# ATJ3315Recorder.net
KiCad netlist of a schematic drawn in EAGLE
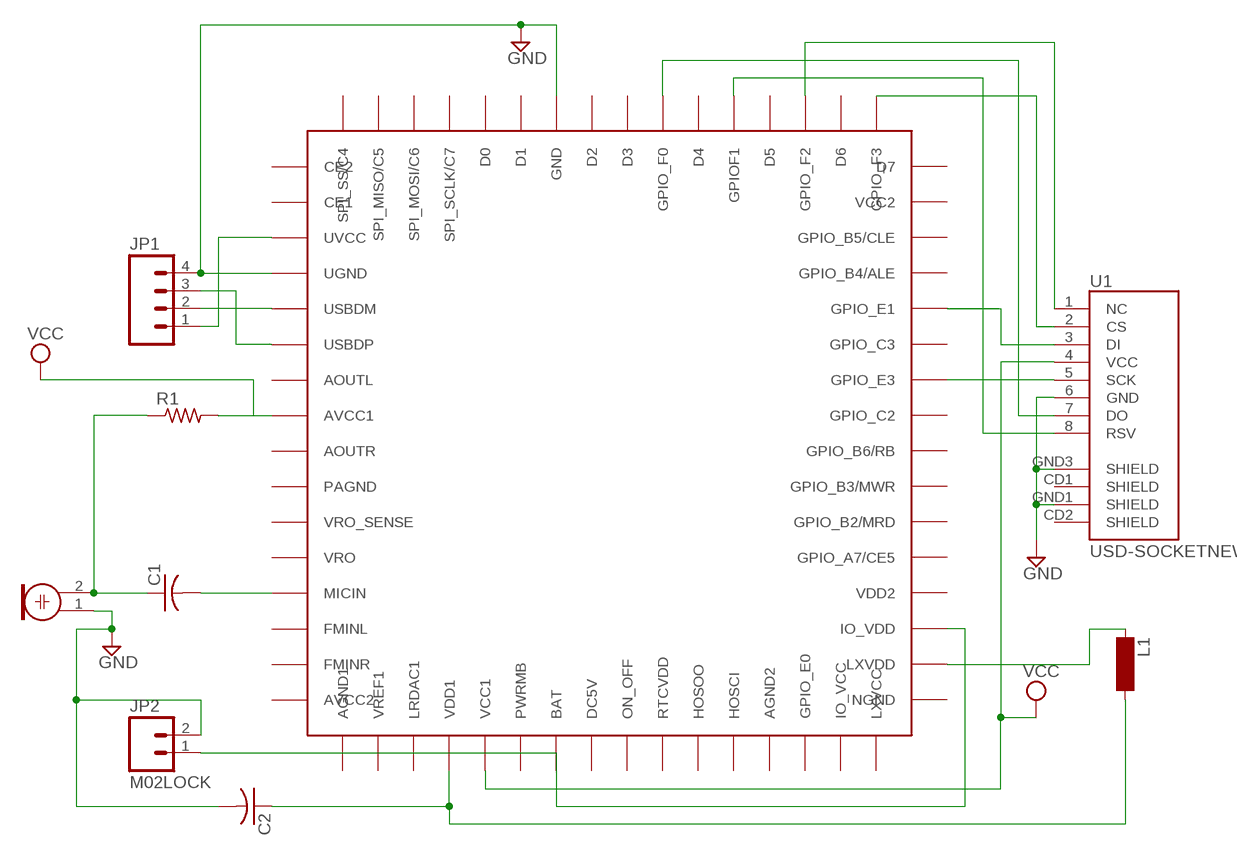
[diagram p0: schematic, sheet 1]

(export (version "E")
  (design (tool "Eeschema 10.0.6"))
  (components
    (comp (ref "C1")
      (value "C-USC0201")
      (footprint "eagle-import:C0201")
      (libsource (lib "eagle-import") (part "C-USC0201"))
    )
    (comp (ref "C2")
      (value "C-USC0201")
      (footprint "eagle-import:C0201")
      (libsource (lib "eagle-import") (part "C-USC0201"))
    )
    (comp (ref "JP1")
      (value "M04PTH")
      (footprint "eagle-import:1X04")
      (libsource (lib "eagle-import") (part "M04PTH"))
    )
    (comp (ref "JP2")
      (value "M02LOCK")
      (footprint "eagle-import:1X02_LOCK")
      (libsource (lib "eagle-import") (part "M02LOCK"))
    )
    (comp (ref "L1")
      (value "SM-1206")
      (footprint "eagle-import:SM-1206")
      (libsource (lib "eagle-import") (part "SM-1206"))
    )
    (comp (ref "M1")
      (value "ELECTRET_MICROPHON-WM-61A")
      (footprint "eagle-import:WM-61A")
      (libsource (lib "eagle-import") (part "ELECTRET_MICROPHON-WM-61A"))
    )
    (comp (ref "R1")
      (value "R-US_M0805")
      (footprint "eagle-import:M0805")
      (libsource (lib "eagle-import") (part "R-US_M0805"))
    )
    (comp (ref "U$4")
      (value "AJ3315")
      (footprint "eagle-import:64M1")
      (libsource (lib "eagle-import") (part "AJ3315"))
    )
    (comp (ref "U1")
      (value "USD-SOCKETNEW")
      (footprint "eagle-import:MICRO-SD-SOCKET-PP")
      (libsource (lib "eagle-import") (part "USD-SOCKETNEW"))
    )
  )
  (nets
    (net (code "1") (name "GND") (class "Default")
      (node (ref "C2") (pin "2") (pinfunction "2_2") (pintype "passive"))
      (node (ref "JP1") (pin "4") (pinfunction "4_4") (pintype "passive"))
      (node (ref "JP2") (pin "2") (pinfunction "2_2") (pintype "passive"))
      (node (ref "M1") (pin "1") (pinfunction "1_1") (pintype "passive"))
      (node (ref "U$4") (pin "4") (pinfunction "UGND_4") (pintype "bidirectional"))
      (node (ref "U$4") (pin "58") (pinfunction "GND_58") (pintype "bidirectional"))
      (node (ref "U1") (pin "6") (pinfunction "GND_6") (pintype "bidirectional"))
      (node (ref "U1") (pin "GND1") (pinfunction "SHIELD_GND1") (pintype "bidirectional"))
      (node (ref "U1") (pin "GND3") (pinfunction "SHIELD_GND3") (pintype "bidirectional"))
    )
    (net (code "2") (name "Net-(C1-Pad1)") (class "Default")
      (node (ref "C1") (pin "1") (pinfunction "1_1") (pintype "passive"))
      (node (ref "M1") (pin "2") (pinfunction "2_2") (pintype "passive"))
      (node (ref "R1") (pin "1") (pinfunction "1_1") (pintype "passive"))
    )
    (net (code "3") (name "Net-(U$4-AVCC1)") (class "Default")
      (node (ref "R1") (pin "2") (pinfunction "2_2") (pintype "passive"))
      (node (ref "U$4") (pin "8") (pinfunction "AVCC1_8") (pintype "bidirectional"))
    )
    (net (code "4") (name "Net-(U$4-BAT)") (class "Default")
      (node (ref "JP2") (pin "1") (pinfunction "1_1") (pintype "passive"))
      (node (ref "U$4") (pin "23") (pinfunction "BAT_23") (pintype "bidirectional"))
      (node (ref "U$4") (pin "35") (pinfunction "IO_VDD_35") (pintype "bidirectional"))
    )
    (net (code "5") (name "Net-(U$4-GPIOF1)") (class "Default")
      (node (ref "U$4") (pin "53") (pinfunction "GPIOF1_53") (pintype "bidirectional"))
      (node (ref "U1") (pin "8") (pinfunction "RSV_8") (pintype "bidirectional"))
    )
    (net (code "6") (name "Net-(U$4-GPIO_E1)") (class "Default")
      (node (ref "U$4") (pin "44") (pinfunction "GPIO_E1_44") (pintype "bidirectional"))
      (node (ref "U1") (pin "3") (pinfunction "DI_3") (pintype "bidirectional"))
    )
    (net (code "7") (name "Net-(U$4-GPIO_E3)") (class "Default")
      (node (ref "U$4") (pin "42") (pinfunction "GPIO_E3_42") (pintype "bidirectional"))
      (node (ref "U1") (pin "5") (pinfunction "SCK_5") (pintype "bidirectional"))
    )
    (net (code "8") (name "Net-(U$4-GPIO_F0)") (class "Default")
      (node (ref "U$4") (pin "55") (pinfunction "GPIO_F0_55") (pintype "bidirectional"))
      (node (ref "U1") (pin "7") (pinfunction "DO_7") (pintype "bidirectional"))
    )
    (net (code "9") (name "Net-(U$4-GPIO_F2)") (class "Default")
      (node (ref "U$4") (pin "51") (pinfunction "GPIO_F2_51") (pintype "bidirectional"))
      (node (ref "U1") (pin "1") (pinfunction "NC_1") (pintype "bidirectional"))
    )
    (net (code "10") (name "Net-(U$4-GPIO_F3)") (class "Default")
      (node (ref "U$4") (pin "49") (pinfunction "GPIO_F3_49") (pintype "bidirectional"))
      (node (ref "U1") (pin "2") (pinfunction "CS_2") (pintype "bidirectional"))
    )
    (net (code "11") (name "Net-(U$4-LXVDD)") (class "Default")
      (node (ref "L1") (pin "1") (pinfunction "1_1") (pintype "passive"))
      (node (ref "U$4") (pin "34") (pinfunction "LXVDD_34") (pintype "bidirectional"))
    )
    (net (code "12") (name "Net-(U$4-MICIN)") (class "Default")
      (node (ref "C1") (pin "2") (pinfunction "2_2") (pintype "passive"))
      (node (ref "U$4") (pin "13") (pinfunction "MICIN_13") (pintype "bidirectional"))
    )
    (net (code "13") (name "Net-(U$4-USBDM)") (class "Default")
      (node (ref "JP1") (pin "2") (pinfunction "2_2") (pintype "passive"))
      (node (ref "U$4") (pin "5") (pinfunction "USBDM_5") (pintype "bidirectional"))
    )
    (net (code "14") (name "Net-(U$4-USBDP)") (class "Default")
      (node (ref "JP1") (pin "3") (pinfunction "3_3") (pintype "passive"))
      (node (ref "U$4") (pin "6") (pinfunction "USBDP_6") (pintype "bidirectional"))
    )
    (net (code "15") (name "Net-(U$4-UVCC)") (class "Default")
      (node (ref "JP1") (pin "1") (pinfunction "1_1") (pintype "passive"))
      (node (ref "U$4") (pin "3") (pinfunction "UVCC_3") (pintype "bidirectional"))
    )
    (net (code "16") (name "Net-(U$4-VDD1)") (class "Default")
      (node (ref "C2") (pin "1") (pinfunction "1_1") (pintype "passive"))
      (node (ref "L1") (pin "2") (pinfunction "2_2") (pintype "passive"))
      (node (ref "U$4") (pin "20") (pinfunction "VDD1_20") (pintype "bidirectional"))
    )
    (net (code "17") (name "VCC") (class "Default")
      (node (ref "U$4") (pin "21") (pinfunction "VCC1_21") (pintype "bidirectional"))
      (node (ref "U1") (pin "4") (pinfunction "VCC_4") (pintype "bidirectional"))
    )
    (net (code "18") (name "unconnected-(U$4-AGND1-Pad17)") (class "Default")
      (node (ref "U$4") (pin "17") (pinfunction "AGND1_17") (pintype "bidirectional"))
    )
    (net (code "19") (name "unconnected-(U$4-AGND2-Pad29)") (class "Default")
      (node (ref "U$4") (pin "29") (pinfunction "AGND2_29") (pintype "bidirectional"))
    )
    (net (code "20") (name "unconnected-(U$4-AOUTL-Pad7)") (class "Default")
      (node (ref "U$4") (pin "7") (pinfunction "AOUTL_7") (pintype "bidirectional"))
    )
    (net (code "21") (name "unconnected-(U$4-AOUTR-Pad9)") (class "Default")
      (node (ref "U$4") (pin "9") (pinfunction "AOUTR_9") (pintype "bidirectional"))
    )
    (net (code "22") (name "unconnected-(U$4-AVCC2-Pad16)") (class "Default")
      (node (ref "U$4") (pin "16") (pinfunction "AVCC2_16") (pintype "bidirectional"))
    )
    (net (code "23") (name "unconnected-(U$4-CE1-Pad2)") (class "Default")
      (node (ref "U$4") (pin "2") (pinfunction "CE1_2") (pintype "bidirectional"))
    )
    (net (code "24") (name "unconnected-(U$4-CE2-Pad1)") (class "Default")
      (node (ref "U$4") (pin "1") (pinfunction "CE2_1") (pintype "bidirectional"))
    )
    (net (code "25") (name "unconnected-(U$4-D0-Pad60)") (class "Default")
      (node (ref "U$4") (pin "60") (pinfunction "D0_60") (pintype "bidirectional"))
    )
    (net (code "26") (name "unconnected-(U$4-D1-Pad59)") (class "Default")
      (node (ref "U$4") (pin "59") (pinfunction "D1_59") (pintype "bidirectional"))
    )
    (net (code "27") (name "unconnected-(U$4-D2-Pad57)") (class "Default")
      (node (ref "U$4") (pin "57") (pinfunction "D2_57") (pintype "bidirectional"))
    )
    (net (code "28") (name "unconnected-(U$4-D3-Pad56)") (class "Default")
      (node (ref "U$4") (pin "56") (pinfunction "D3_56") (pintype "bidirectional"))
    )
    (net (code "29") (name "unconnected-(U$4-D4-Pad54)") (class "Default")
      (node (ref "U$4") (pin "54") (pinfunction "D4_54") (pintype "bidirectional"))
    )
    (net (code "30") (name "unconnected-(U$4-D5-Pad52)") (class "Default")
      (node (ref "U$4") (pin "52") (pinfunction "D5_52") (pintype "bidirectional"))
    )
    (net (code "31") (name "unconnected-(U$4-D6-Pad50)") (class "Default")
      (node (ref "U$4") (pin "50") (pinfunction "D6_50") (pintype "bidirectional"))
    )
    (net (code "32") (name "unconnected-(U$4-D7-Pad48)") (class "Default")
      (node (ref "U$4") (pin "48") (pinfunction "D7_48") (pintype "bidirectional"))
    )
    (net (code "33") (name "unconnected-(U$4-DC5V-Pad24)") (class "Default")
      (node (ref "U$4") (pin "24") (pinfunction "DC5V_24") (pintype "bidirectional"))
    )
    (net (code "34") (name "unconnected-(U$4-FMINL-Pad14)") (class "Default")
      (node (ref "U$4") (pin "14") (pinfunction "FMINL_14") (pintype "bidirectional"))
    )
    (net (code "35") (name "unconnected-(U$4-FMINR-Pad15)") (class "Default")
      (node (ref "U$4") (pin "15") (pinfunction "FMINR_15") (pintype "bidirectional"))
    )
    (net (code "36") (name "unconnected-(U$4-GPIO_A7{slash}CE5-Pad37)") (class "Default")
      (node (ref "U$4") (pin "37") (pinfunction "GPIO_A7/CE5_37") (pintype "bidirectional"))
    )
    (net (code "37") (name "unconnected-(U$4-GPIO_B2{slash}MRD-Pad38)") (class "Default")
      (node (ref "U$4") (pin "38") (pinfunction "GPIO_B2/MRD_38") (pintype "bidirectional"))
    )
    (net (code "38") (name "unconnected-(U$4-GPIO_B3{slash}MWR-Pad39)") (class "Default")
      (node (ref "U$4") (pin "39") (pinfunction "GPIO_B3/MWR_39") (pintype "bidirectional"))
    )
    (net (code "39") (name "unconnected-(U$4-GPIO_B4{slash}ALE-Pad45)") (class "Default")
      (node (ref "U$4") (pin "45") (pinfunction "GPIO_B4/ALE_45") (pintype "bidirectional"))
    )
    (net (code "40") (name "unconnected-(U$4-GPIO_B5{slash}CLE-Pad46)") (class "Default")
      (node (ref "U$4") (pin "46") (pinfunction "GPIO_B5/CLE_46") (pintype "bidirectional"))
    )
    (net (code "41") (name "unconnected-(U$4-GPIO_B6{slash}RB-Pad40)") (class "Default")
      (node (ref "U$4") (pin "40") (pinfunction "GPIO_B6/RB_40") (pintype "bidirectional"))
    )
    (net (code "42") (name "unconnected-(U$4-GPIO_C2-Pad41)") (class "Default")
      (node (ref "U$4") (pin "41") (pinfunction "GPIO_C2_41") (pintype "bidirectional"))
    )
    (net (code "43") (name "unconnected-(U$4-GPIO_C3-Pad43)") (class "Default")
      (node (ref "U$4") (pin "43") (pinfunction "GPIO_C3_43") (pintype "bidirectional"))
    )
    (net (code "44") (name "unconnected-(U$4-GPIO_E0-Pad30)") (class "Default")
      (node (ref "U$4") (pin "30") (pinfunction "GPIO_E0_30") (pintype "bidirectional"))
    )
    (net (code "45") (name "unconnected-(U$4-HOSCI-Pad28)") (class "Default")
      (node (ref "U$4") (pin "28") (pinfunction "HOSCI_28") (pintype "bidirectional"))
    )
    (net (code "46") (name "unconnected-(U$4-HOSOO-Pad27)") (class "Default")
      (node (ref "U$4") (pin "27") (pinfunction "HOSOO_27") (pintype "bidirectional"))
    )
    (net (code "47") (name "unconnected-(U$4-IO_VCC-Pad31)") (class "Default")
      (node (ref "U$4") (pin "31") (pinfunction "IO_VCC_31") (pintype "bidirectional"))
    )
    (net (code "48") (name "unconnected-(U$4-LRDAC1-Pad19)") (class "Default")
      (node (ref "U$4") (pin "19") (pinfunction "LRDAC1_19") (pintype "bidirectional"))
    )
    (net (code "49") (name "unconnected-(U$4-LXVCC-Pad32)") (class "Default")
      (node (ref "U$4") (pin "32") (pinfunction "LXVCC_32") (pintype "bidirectional"))
    )
    (net (code "50") (name "unconnected-(U$4-NGND-Pad33)") (class "Default")
      (node (ref "U$4") (pin "33") (pinfunction "NGND_33") (pintype "bidirectional"))
    )
    (net (code "51") (name "unconnected-(U$4-ON_OFF-Pad25)") (class "Default")
      (node (ref "U$4") (pin "25") (pinfunction "ON_OFF_25") (pintype "bidirectional"))
    )
    (net (code "52") (name "unconnected-(U$4-PAGND-Pad10)") (class "Default")
      (node (ref "U$4") (pin "10") (pinfunction "PAGND_10") (pintype "bidirectional"))
    )
    (net (code "53") (name "unconnected-(U$4-PWRMB-Pad22)") (class "Default")
      (node (ref "U$4") (pin "22") (pinfunction "PWRMB_22") (pintype "bidirectional"))
    )
    (net (code "54") (name "unconnected-(U$4-RTCVDD-Pad26)") (class "Default")
      (node (ref "U$4") (pin "26") (pinfunction "RTCVDD_26") (pintype "bidirectional"))
    )
    (net (code "55") (name "unconnected-(U$4-SPI_MISO{slash}C5-Pad63)") (class "Default")
      (node (ref "U$4") (pin "63") (pinfunction "SPI_MISO/C5_63") (pintype "bidirectional"))
    )
    (net (code "56") (name "unconnected-(U$4-SPI_MOSI{slash}C6-Pad62)") (class "Default")
      (node (ref "U$4") (pin "62") (pinfunction "SPI_MOSI/C6_62") (pintype "bidirectional"))
    )
    (net (code "57") (name "unconnected-(U$4-SPI_SCLK{slash}C7-Pad61)") (class "Default")
      (node (ref "U$4") (pin "61") (pinfunction "SPI_SCLK/C7_61") (pintype "bidirectional"))
    )
    (net (code "58") (name "unconnected-(U$4-SPI_SS{slash}C4-Pad64)") (class "Default")
      (node (ref "U$4") (pin "64") (pinfunction "SPI_SS/C4_64") (pintype "bidirectional"))
    )
    (net (code "59") (name "unconnected-(U$4-VCC2-Pad47)") (class "Default")
      (node (ref "U$4") (pin "47") (pinfunction "VCC2_47") (pintype "bidirectional"))
    )
    (net (code "60") (name "unconnected-(U$4-VDD2-Pad36)") (class "Default")
      (node (ref "U$4") (pin "36") (pinfunction "VDD2_36") (pintype "bidirectional"))
    )
    (net (code "61") (name "unconnected-(U$4-VREF1-Pad18)") (class "Default")
      (node (ref "U$4") (pin "18") (pinfunction "VREF1_18") (pintype "bidirectional"))
    )
    (net (code "62") (name "unconnected-(U$4-VRO-Pad12)") (class "Default")
      (node (ref "U$4") (pin "12") (pinfunction "VRO_12") (pintype "bidirectional"))
    )
    (net (code "63") (name "unconnected-(U$4-VRO_SENSE-Pad11)") (class "Default")
      (node (ref "U$4") (pin "11") (pinfunction "VRO_SENSE_11") (pintype "bidirectional"))
    )
    (net (code "64") (name "unconnected-(U1-SHIELD-PadCD1)") (class "Default")
      (node (ref "U1") (pin "CD1") (pinfunction "SHIELD_CD1") (pintype "bidirectional"))
    )
    (net (code "65") (name "unconnected-(U1-SHIELD-PadCD2)") (class "Default")
      (node (ref "U1") (pin "CD2") (pinfunction "SHIELD_CD2") (pintype "bidirectional"))
    )
  )
)
